# Control_Unit.net
KiCad netlist of a schematic drawn in EAGLE
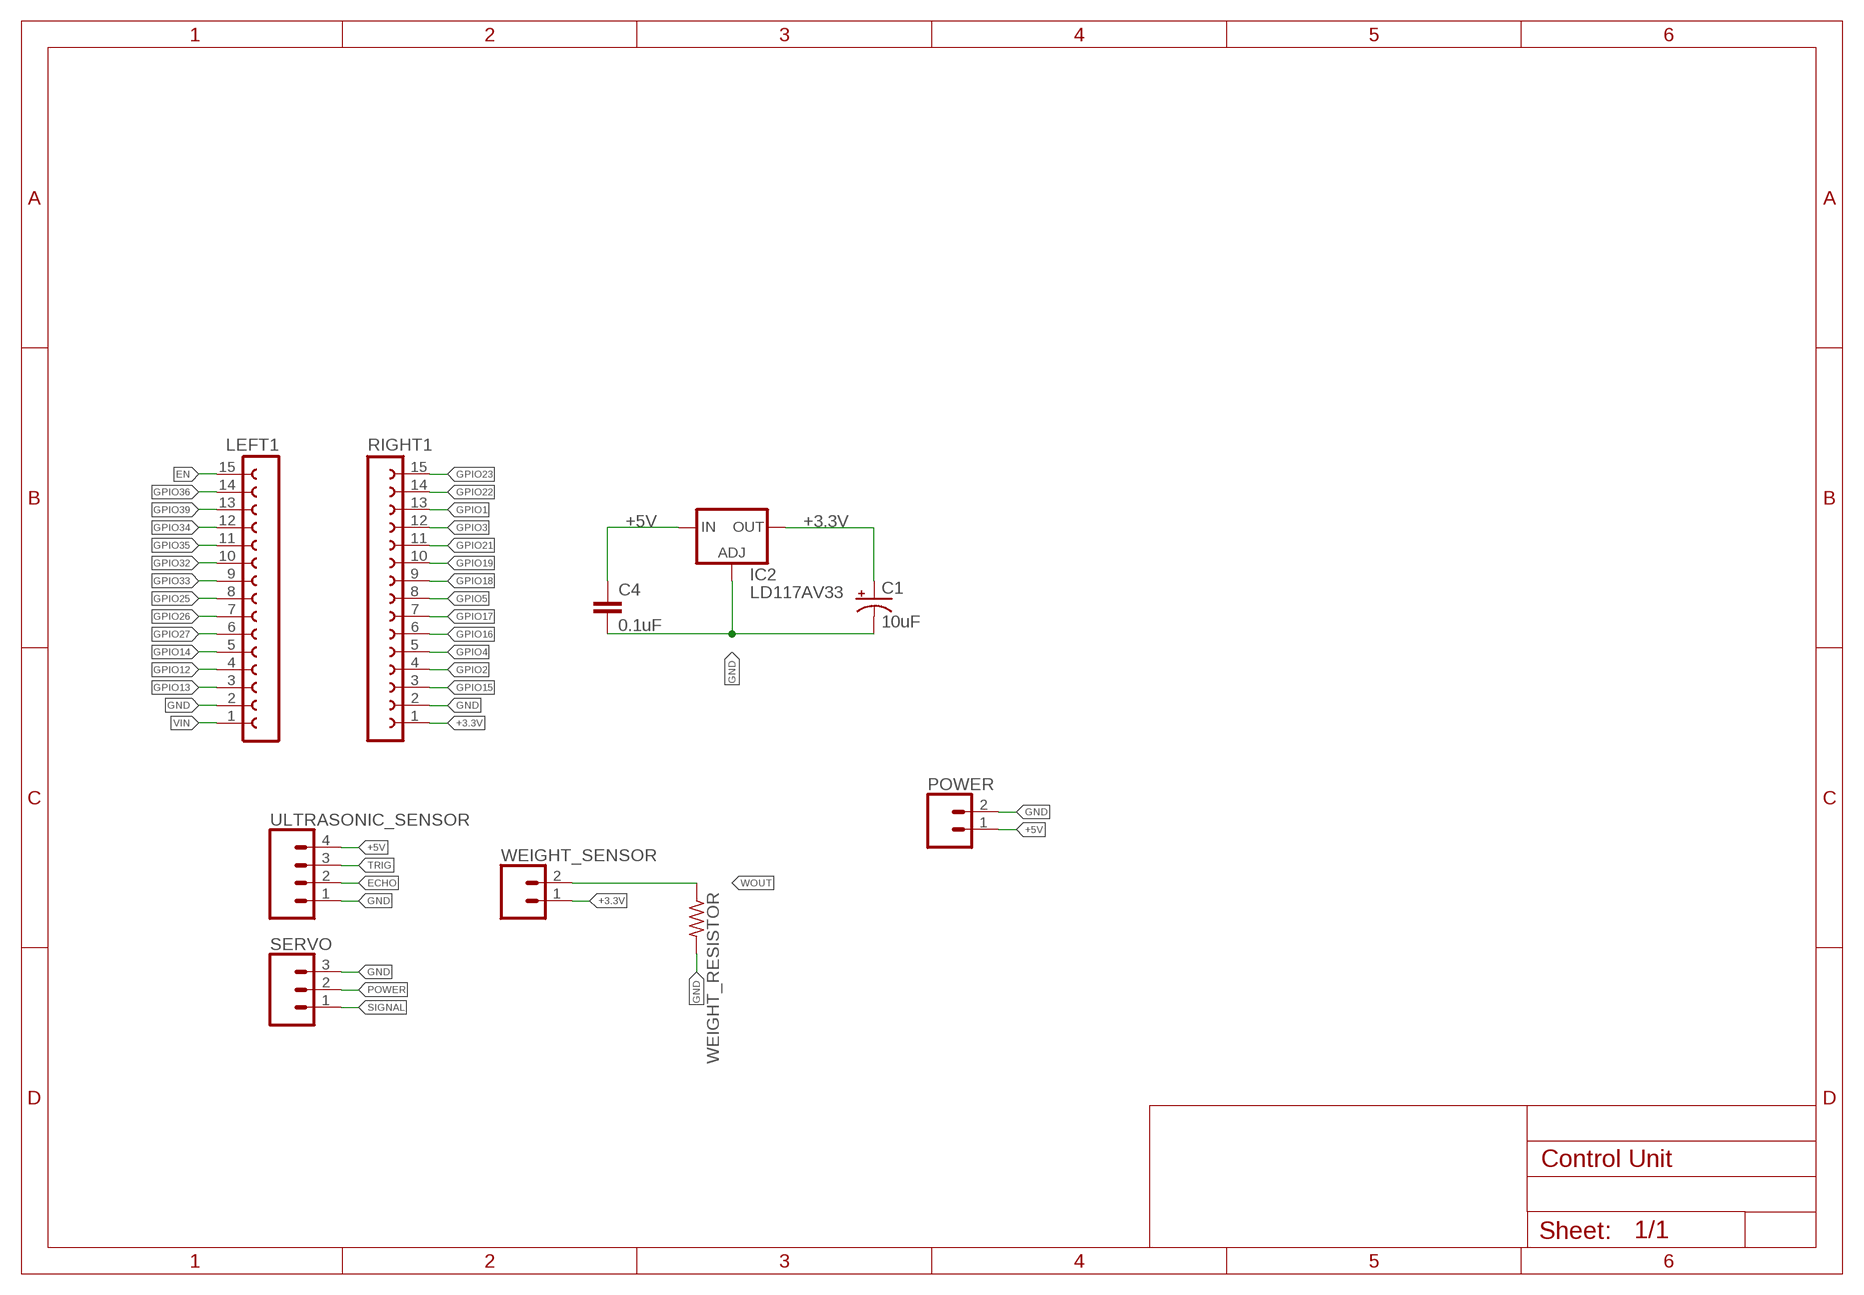
[diagram p0: schematic, sheet 1]

(export (version "E")
  (design (tool "Eeschema 10.0.6"))
  (components
    (comp (ref "C1")
      (value "10uF")
      (footprint "eagle-import:CPOL-RADIAL-2.5MM-5MM-KIT")
      (libsource (lib "eagle-import") (part "10UF-POLAR-RADIAL-2.5MM-KIT-25V-20%"))
    )
    (comp (ref "C4")
      (value "0.1uF")
      (footprint "eagle-import:CAP-PTH-SMALL-KIT")
      (libsource (lib "eagle-import") (part "0.1UF-KIT-EZ-50V-20%"))
    )
    (comp (ref "IC2")
      (value "LD117AV33")
      (footprint "eagle-import:TO220L1")
      (libsource (lib "eagle-import") (part "LD117A?V33"))
    )
    (comp (ref "LEFT1")
      (value "FE15-1")
      (footprint "eagle-import:FE15")
      (fields (field (name "SPICEPREFIX") "X"))
      (libsource (lib "eagle-import") (part "FE15-1"))
    )
    (comp (ref "POWER")
      (value "CONN_02LOCK_LONGPADS")
      (footprint "eagle-import:1X02_LOCK_LONGPADS")
      (libsource (lib "eagle-import") (part "CONN_02LOCK_LONGPADS"))
    )
    (comp (ref "RIGHT1")
      (value "FE15-1")
      (footprint "eagle-import:FE15")
      (fields (field (name "SPICEPREFIX") "X"))
      (libsource (lib "eagle-import") (part "FE15-1"))
    )
    (comp (ref "SERVO")
      (value "CONN_03LONGPADS")
      (footprint "eagle-import:1X03_LONGPADS")
      (libsource (lib "eagle-import") (part "CONN_03LONGPADS"))
    )
    (comp (ref "ULTRASONIC_SENSOR")
      (value "CONN_04LONGPADS")
      (footprint "eagle-import:1X04_LONGPADS")
      (libsource (lib "eagle-import") (part "CONN_04LONGPADS"))
    )
    (comp (ref "WEIGHT_RESISTOR")
      (value "R-US_0207/7")
      (footprint "eagle-import:0207_7")
      (libsource (lib "eagle-import") (part "R-US_0207/7"))
    )
    (comp (ref "WEIGHT_SENSOR")
      (value "CONN_02LOCK_LONGPADS")
      (footprint "eagle-import:1X02_LOCK_LONGPADS")
      (libsource (lib "eagle-import") (part "CONN_02LOCK_LONGPADS"))
    )
  )
  (nets
    (net (code "1") (name "+3.3V") (class "Default")
      (node (ref "C1") (pin "1") (pinfunction "+_1") (pintype "passive"))
      (node (ref "IC2") (pin "2") (pinfunction "OUT_2") (pintype "passive"))
      (node (ref "RIGHT1") (pin "1") (pinfunction "1_1") (pintype "passive"))
      (node (ref "WEIGHT_SENSOR") (pin "1") (pinfunction "1_1") (pintype "passive"))
    )
    (net (code "2") (name "+5V") (class "Default")
      (node (ref "C4") (pin "1") (pinfunction "1_1") (pintype "passive"))
      (node (ref "IC2") (pin "3") (pinfunction "IN_3") (pintype "input"))
      (node (ref "POWER") (pin "1") (pinfunction "1_1") (pintype "passive"))
      (node (ref "ULTRASONIC_SENSOR") (pin "4") (pinfunction "4_4") (pintype "passive"))
    )
    (net (code "3") (name "ECHO") (class "Default")
      (node (ref "ULTRASONIC_SENSOR") (pin "2") (pinfunction "2_2") (pintype "passive"))
    )
    (net (code "4") (name "EN") (class "Default")
      (node (ref "LEFT1") (pin "15") (pinfunction "15_15") (pintype "passive"))
    )
    (net (code "5") (name "GND") (class "Default")
      (node (ref "C1") (pin "2") (pinfunction "-_2") (pintype "passive"))
      (node (ref "C4") (pin "2") (pinfunction "2_2") (pintype "passive"))
      (node (ref "IC2") (pin "1") (pinfunction "ADJ_1") (pintype "input"))
      (node (ref "LEFT1") (pin "2") (pinfunction "2_2") (pintype "passive"))
      (node (ref "POWER") (pin "2") (pinfunction "2_2") (pintype "passive"))
      (node (ref "RIGHT1") (pin "2") (pinfunction "2_2") (pintype "passive"))
      (node (ref "SERVO") (pin "3") (pinfunction "3_3") (pintype "passive"))
      (node (ref "ULTRASONIC_SENSOR") (pin "1") (pinfunction "1_1") (pintype "passive"))
      (node (ref "WEIGHT_RESISTOR") (pin "2") (pinfunction "2_2") (pintype "passive"))
    )
    (net (code "6") (name "GPIO1") (class "Default")
      (node (ref "RIGHT1") (pin "13") (pinfunction "13_13") (pintype "passive"))
    )
    (net (code "7") (name "GPIO2") (class "Default")
      (node (ref "RIGHT1") (pin "4") (pinfunction "4_4") (pintype "passive"))
    )
    (net (code "8") (name "GPIO3") (class "Default")
      (node (ref "RIGHT1") (pin "12") (pinfunction "12_12") (pintype "passive"))
    )
    (net (code "9") (name "GPIO4") (class "Default")
      (node (ref "RIGHT1") (pin "5") (pinfunction "5_5") (pintype "passive"))
    )
    (net (code "10") (name "GPIO5") (class "Default")
      (node (ref "RIGHT1") (pin "8") (pinfunction "8_8") (pintype "passive"))
    )
    (net (code "11") (name "GPIO12") (class "Default")
      (node (ref "LEFT1") (pin "4") (pinfunction "4_4") (pintype "passive"))
    )
    (net (code "12") (name "GPIO13") (class "Default")
      (node (ref "LEFT1") (pin "3") (pinfunction "3_3") (pintype "passive"))
    )
    (net (code "13") (name "GPIO14") (class "Default")
      (node (ref "LEFT1") (pin "5") (pinfunction "5_5") (pintype "passive"))
    )
    (net (code "14") (name "GPIO15") (class "Default")
      (node (ref "RIGHT1") (pin "3") (pinfunction "3_3") (pintype "passive"))
    )
    (net (code "15") (name "GPIO16") (class "Default")
      (node (ref "RIGHT1") (pin "6") (pinfunction "6_6") (pintype "passive"))
    )
    (net (code "16") (name "GPIO17") (class "Default")
      (node (ref "RIGHT1") (pin "7") (pinfunction "7_7") (pintype "passive"))
    )
    (net (code "17") (name "GPIO18") (class "Default")
      (node (ref "RIGHT1") (pin "9") (pinfunction "9_9") (pintype "passive"))
    )
    (net (code "18") (name "GPIO19") (class "Default")
      (node (ref "RIGHT1") (pin "10") (pinfunction "10_10") (pintype "passive"))
    )
    (net (code "19") (name "GPIO21") (class "Default")
      (node (ref "RIGHT1") (pin "11") (pinfunction "11_11") (pintype "passive"))
    )
    (net (code "20") (name "GPIO22") (class "Default")
      (node (ref "RIGHT1") (pin "14") (pinfunction "14_14") (pintype "passive"))
    )
    (net (code "21") (name "GPIO23") (class "Default")
      (node (ref "RIGHT1") (pin "15") (pinfunction "15_15") (pintype "passive"))
    )
    (net (code "22") (name "GPIO25") (class "Default")
      (node (ref "LEFT1") (pin "8") (pinfunction "8_8") (pintype "passive"))
    )
    (net (code "23") (name "GPIO26") (class "Default")
      (node (ref "LEFT1") (pin "7") (pinfunction "7_7") (pintype "passive"))
    )
    (net (code "24") (name "GPIO27") (class "Default")
      (node (ref "LEFT1") (pin "6") (pinfunction "6_6") (pintype "passive"))
    )
    (net (code "25") (name "GPIO32") (class "Default")
      (node (ref "LEFT1") (pin "10") (pinfunction "10_10") (pintype "passive"))
    )
    (net (code "26") (name "GPIO33") (class "Default")
      (node (ref "LEFT1") (pin "9") (pinfunction "9_9") (pintype "passive"))
    )
    (net (code "27") (name "GPIO34") (class "Default")
      (node (ref "LEFT1") (pin "12") (pinfunction "12_12") (pintype "passive"))
    )
    (net (code "28") (name "GPIO35") (class "Default")
      (node (ref "LEFT1") (pin "11") (pinfunction "11_11") (pintype "passive"))
    )
    (net (code "29") (name "GPIO36") (class "Default")
      (node (ref "LEFT1") (pin "14") (pinfunction "14_14") (pintype "passive"))
    )
    (net (code "30") (name "GPIO39") (class "Default")
      (node (ref "LEFT1") (pin "13") (pinfunction "13_13") (pintype "passive"))
    )
    (net (code "31") (name "POWER") (class "Default")
      (node (ref "SERVO") (pin "2") (pinfunction "2_2") (pintype "passive"))
    )
    (net (code "32") (name "SIGNAL") (class "Default")
      (node (ref "SERVO") (pin "1") (pinfunction "1_1") (pintype "passive"))
    )
    (net (code "33") (name "TRIG") (class "Default")
      (node (ref "ULTRASONIC_SENSOR") (pin "3") (pinfunction "3_3") (pintype "passive"))
    )
    (net (code "34") (name "VIN") (class "Default")
      (node (ref "LEFT1") (pin "1") (pinfunction "1_1") (pintype "passive"))
    )
    (net (code "35") (name "WOUT") (class "Default")
      (node (ref "WEIGHT_RESISTOR") (pin "1") (pinfunction "1_1") (pintype "passive"))
      (node (ref "WEIGHT_SENSOR") (pin "2") (pinfunction "2_2") (pintype "passive"))
    )
  )
)
